# Sheet1.net
KiCad netlist of a schematic drawn in Altium Designer
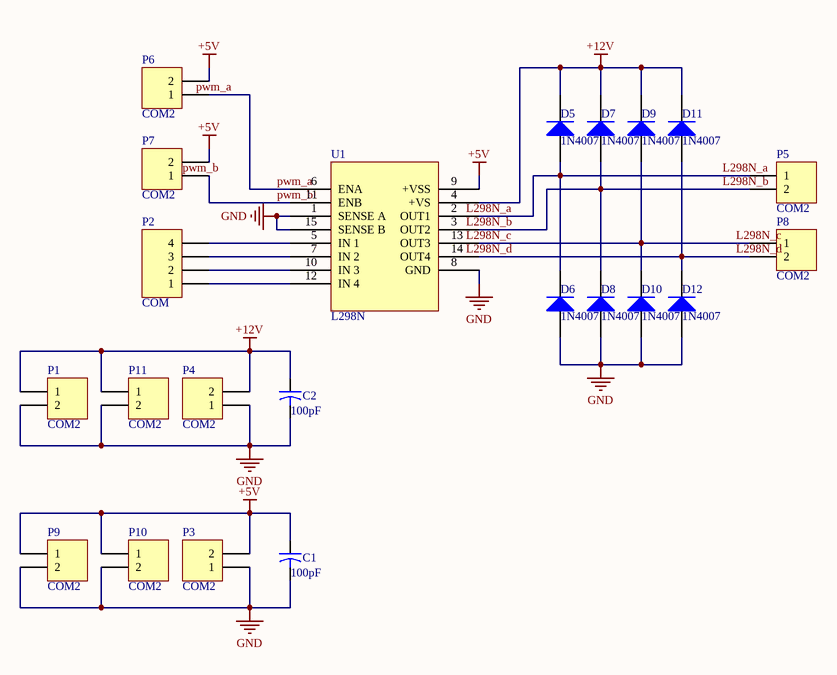
[diagram p0: Sheet1.SchDoc]

(export (version "E")
  (design (tool "Eeschema 10.0.6"))
  (components
    (comp (ref "C1")
      (value "100pF")
      (footprint "CAPR5-4X5")
      (description "Capacitor")
      (fields (field (name "PUBLISHER") "Altium Limited"))
      (libsource (lib "Miscellaneous Devices") (part "Cap2"))
    )
    (comp (ref "C2")
      (value "100pF")
      (footprint "CAPR5-4X5")
      (description "Capacitor")
      (fields (field (name "PUBLISHER") "Altium Limited"))
      (libsource (lib "Miscellaneous Devices") (part "Cap2"))
    )
    (comp (ref "D5")
      (value "1N4007")
      (footprint "DO-41")
      (description "1 Amp General Purpose Rectifier")
      (fields (field (name "PUBLISHER") "Altium Limited"))
      (libsource (lib "Miscellaneous Devices") (part "Diode 1N4007"))
    )
    (comp (ref "D6")
      (value "1N4007")
      (footprint "DO-41")
      (description "1 Amp General Purpose Rectifier")
      (fields (field (name "PUBLISHER") "Altium Limited"))
      (libsource (lib "Miscellaneous Devices") (part "Diode 1N4007"))
    )
    (comp (ref "D7")
      (value "1N4007")
      (footprint "DO-41")
      (description "1 Amp General Purpose Rectifier")
      (fields (field (name "PUBLISHER") "Altium Limited"))
      (libsource (lib "Miscellaneous Devices") (part "Diode 1N4007"))
    )
    (comp (ref "D8")
      (value "1N4007")
      (footprint "DO-41")
      (description "1 Amp General Purpose Rectifier")
      (fields (field (name "PUBLISHER") "Altium Limited"))
      (libsource (lib "Miscellaneous Devices") (part "Diode 1N4007"))
    )
    (comp (ref "D9")
      (value "1N4007")
      (footprint "DO-41")
      (description "1 Amp General Purpose Rectifier")
      (fields (field (name "PUBLISHER") "Altium Limited"))
      (libsource (lib "Miscellaneous Devices") (part "Diode 1N4007"))
    )
    (comp (ref "D10")
      (value "1N4007")
      (footprint "DO-41")
      (description "1 Amp General Purpose Rectifier")
      (fields (field (name "PUBLISHER") "Altium Limited"))
      (libsource (lib "Miscellaneous Devices") (part "Diode 1N4007"))
    )
    (comp (ref "D11")
      (value "1N4007")
      (footprint "DO-41")
      (description "1 Amp General Purpose Rectifier")
      (fields (field (name "PUBLISHER") "Altium Limited"))
      (libsource (lib "Miscellaneous Devices") (part "Diode 1N4007"))
    )
    (comp (ref "D12")
      (value "1N4007")
      (footprint "DO-41")
      (description "1 Amp General Purpose Rectifier")
      (fields (field (name "PUBLISHER") "Altium Limited"))
      (libsource (lib "Miscellaneous Devices") (part "Diode 1N4007"))
    )
    (comp (ref "P1")
      (value "COM2")
      (footprint "HDR1X2")
      (description "Header, 2-Pin")
      (fields (field (name "PUBLISHER") "Altium Limited"))
      (libsource (lib "") (part "Header 2_1"))
    )
    (comp (ref "P2")
      (value "COM")
      (footprint "HDR1X4")
      (description "Header, 4-Pin")
      (fields (field (name "PUBLISHER") "Altium Limited"))
      (libsource (lib "Miscellaneous Connectors") (part "Header 4"))
    )
    (comp (ref "P3")
      (value "COM2")
      (footprint "HDR1X2")
      (description "Header, 2-Pin")
      (fields (field (name "PUBLISHER") "Altium Limited"))
      (libsource (lib "Miscellaneous Connectors") (part "Header 2"))
    )
    (comp (ref "P4")
      (value "COM2")
      (footprint "DP3")
      (description "Header, 2-Pin")
      (fields (field (name "PUBLISHER") "Altium Limited"))
      (libsource (lib "Miscellaneous Connectors") (part "Header 2"))
    )
    (comp (ref "P5")
      (value "COM2")
      (footprint "DP3")
      (description "Header, 2-Pin")
      (fields (field (name "PUBLISHER") "Altium Limited"))
      (libsource (lib "") (part "Header 2_1"))
    )
    (comp (ref "P6")
      (value "COM2")
      (footprint "HDR1X2")
      (description "Header, 2-Pin")
      (fields (field (name "PUBLISHER") "Altium Limited"))
      (libsource (lib "Miscellaneous Connectors") (part "Header 2"))
    )
    (comp (ref "P7")
      (value "COM2")
      (footprint "HDR1X2")
      (description "Header, 2-Pin")
      (fields (field (name "PUBLISHER") "Altium Limited"))
      (libsource (lib "Miscellaneous Connectors") (part "Header 2"))
    )
    (comp (ref "P8")
      (value "COM2")
      (footprint "DP3")
      (description "Header, 2-Pin")
      (fields (field (name "PUBLISHER") "Altium Limited"))
      (libsource (lib "") (part "Header 2_1"))
    )
    (comp (ref "P9")
      (value "COM2")
      (footprint "HDR1X2")
      (description "Header, 2-Pin")
      (fields (field (name "PUBLISHER") "Altium Limited"))
      (libsource (lib "") (part "Header 2_1"))
    )
    (comp (ref "P10")
      (value "COM2")
      (footprint "HDR1X2")
      (description "Header, 2-Pin")
      (fields (field (name "PUBLISHER") "Altium Limited"))
      (libsource (lib "") (part "Header 2_1"))
    )
    (comp (ref "P11")
      (value "COM2")
      (footprint "HDR1X2")
      (description "Header, 2-Pin")
      (fields (field (name "PUBLISHER") "Altium Limited"))
      (libsource (lib "") (part "Header 2_1"))
    )
    (comp (ref "U1") (value "L298N") (footprint "L298N - duplicate") (libsource (lib "KU1") (part "L298N")))
  )
  (nets
    (net (code "1") (name "+5V") (class "Default")
      (node (ref "C1") (pin "1") (pinfunction "1_1") (pintype "passive"))
      (node (ref "P10") (pin "1") (pinfunction "1_1") (pintype "passive"))
      (node (ref "P3") (pin "2") (pinfunction "2_2") (pintype "passive"))
      (node (ref "P6") (pin "2") (pinfunction "2_2") (pintype "passive"))
      (node (ref "P7") (pin "2") (pinfunction "2_2") (pintype "passive"))
      (node (ref "P9") (pin "1") (pinfunction "1_1") (pintype "passive"))
      (node (ref "U1") (pin "9") (pinfunction "+VSS_9") (pintype "passive"))
    )
    (net (code "2") (name "+12V") (class "Default")
      (node (ref "C2") (pin "1") (pinfunction "1_1") (pintype "passive"))
      (node (ref "D11") (pin "2") (pinfunction "K_2") (pintype "passive"))
      (node (ref "D5") (pin "2") (pinfunction "K_2") (pintype "passive"))
      (node (ref "D7") (pin "2") (pinfunction "K_2") (pintype "passive"))
      (node (ref "D9") (pin "2") (pinfunction "K_2") (pintype "passive"))
      (node (ref "P1") (pin "1") (pinfunction "1_1") (pintype "passive"))
      (node (ref "P11") (pin "1") (pinfunction "1_1") (pintype "passive"))
      (node (ref "P4") (pin "2") (pinfunction "2_2") (pintype "passive"))
      (node (ref "U1") (pin "4") (pinfunction "+VS_4") (pintype "passive"))
    )
    (net (code "3") (name "/L298N_a") (class "Default")
      (node (ref "D5") (pin "1") (pinfunction "A_1") (pintype "passive"))
      (node (ref "D6") (pin "2") (pinfunction "K_2") (pintype "passive"))
      (node (ref "P5") (pin "1") (pinfunction "1_1") (pintype "passive"))
      (node (ref "U1") (pin "2") (pinfunction "OUT1_2") (pintype "passive"))
    )
    (net (code "4") (name "/L298N_b") (class "Default")
      (node (ref "D7") (pin "1") (pinfunction "A_1") (pintype "passive"))
      (node (ref "D8") (pin "2") (pinfunction "K_2") (pintype "passive"))
      (node (ref "P5") (pin "2") (pinfunction "2_2") (pintype "passive"))
      (node (ref "U1") (pin "3") (pinfunction "OUT2_3") (pintype "passive"))
    )
    (net (code "5") (name "/L298N_c") (class "Default")
      (node (ref "D10") (pin "2") (pinfunction "K_2") (pintype "passive"))
      (node (ref "D9") (pin "1") (pinfunction "A_1") (pintype "passive"))
      (node (ref "P8") (pin "1") (pinfunction "1_1") (pintype "passive"))
      (node (ref "U1") (pin "13") (pinfunction "OUT3_13") (pintype "passive"))
    )
    (net (code "6") (name "/L298N_d") (class "Default")
      (node (ref "D11") (pin "1") (pinfunction "A_1") (pintype "passive"))
      (node (ref "D12") (pin "2") (pinfunction "K_2") (pintype "passive"))
      (node (ref "P8") (pin "2") (pinfunction "2_2") (pintype "passive"))
      (node (ref "U1") (pin "14") (pinfunction "OUT4_14") (pintype "passive"))
    )
    (net (code "7") (name "/pwm_a") (class "Default")
      (node (ref "P6") (pin "1") (pinfunction "1_1") (pintype "passive"))
      (node (ref "U1") (pin "6") (pinfunction "ENA_6") (pintype "passive"))
    )
    (net (code "8") (name "/pwm_b") (class "Default")
      (node (ref "P7") (pin "1") (pinfunction "1_1") (pintype "passive"))
      (node (ref "U1") (pin "11") (pinfunction "ENB_11") (pintype "passive"))
    )
    (net (code "9") (name "GND") (class "Default")
      (node (ref "C1") (pin "2") (pinfunction "2_2") (pintype "passive"))
      (node (ref "C2") (pin "2") (pinfunction "2_2") (pintype "passive"))
      (node (ref "D10") (pin "1") (pinfunction "A_1") (pintype "passive"))
      (node (ref "D12") (pin "1") (pinfunction "A_1") (pintype "passive"))
      (node (ref "D6") (pin "1") (pinfunction "A_1") (pintype "passive"))
      (node (ref "D8") (pin "1") (pinfunction "A_1") (pintype "passive"))
      (node (ref "P1") (pin "2") (pinfunction "2_2") (pintype "passive"))
      (node (ref "P10") (pin "2") (pinfunction "2_2") (pintype "passive"))
      (node (ref "P11") (pin "2") (pinfunction "2_2") (pintype "passive"))
      (node (ref "P3") (pin "1") (pinfunction "1_1") (pintype "passive"))
      (node (ref "P4") (pin "1") (pinfunction "1_1") (pintype "passive"))
      (node (ref "P9") (pin "2") (pinfunction "2_2") (pintype "passive"))
      (node (ref "U1") (pin "1") (pinfunction "SENSE_A_1") (pintype "passive"))
      (node (ref "U1") (pin "15") (pinfunction "SENSE_B_15") (pintype "passive"))
      (node (ref "U1") (pin "8") (pinfunction "GND_8") (pintype "passive"))
    )
    (net (code "10") (name "Net-(U1-IN_1)") (class "Default")
      (node (ref "P2") (pin "4") (pinfunction "4_4") (pintype "passive"))
      (node (ref "U1") (pin "5") (pinfunction "IN_1_5") (pintype "passive"))
    )
    (net (code "11") (name "Net-(U1-IN_2)") (class "Default")
      (node (ref "P2") (pin "3") (pinfunction "3_3") (pintype "passive"))
      (node (ref "U1") (pin "7") (pinfunction "IN_2_7") (pintype "passive"))
    )
    (net (code "12") (name "Net-(U1-IN_3)") (class "Default")
      (node (ref "P2") (pin "2") (pinfunction "2_2") (pintype "passive"))
      (node (ref "U1") (pin "10") (pinfunction "IN_3_10") (pintype "passive"))
    )
    (net (code "13") (name "Net-(U1-IN_4)") (class "Default")
      (node (ref "P2") (pin "1") (pinfunction "1_1") (pintype "passive"))
      (node (ref "U1") (pin "12") (pinfunction "IN_4_12") (pintype "passive"))
    )
  )
)
